# 31813A.net
KiCad netlist of a schematic drawn in EAGLE
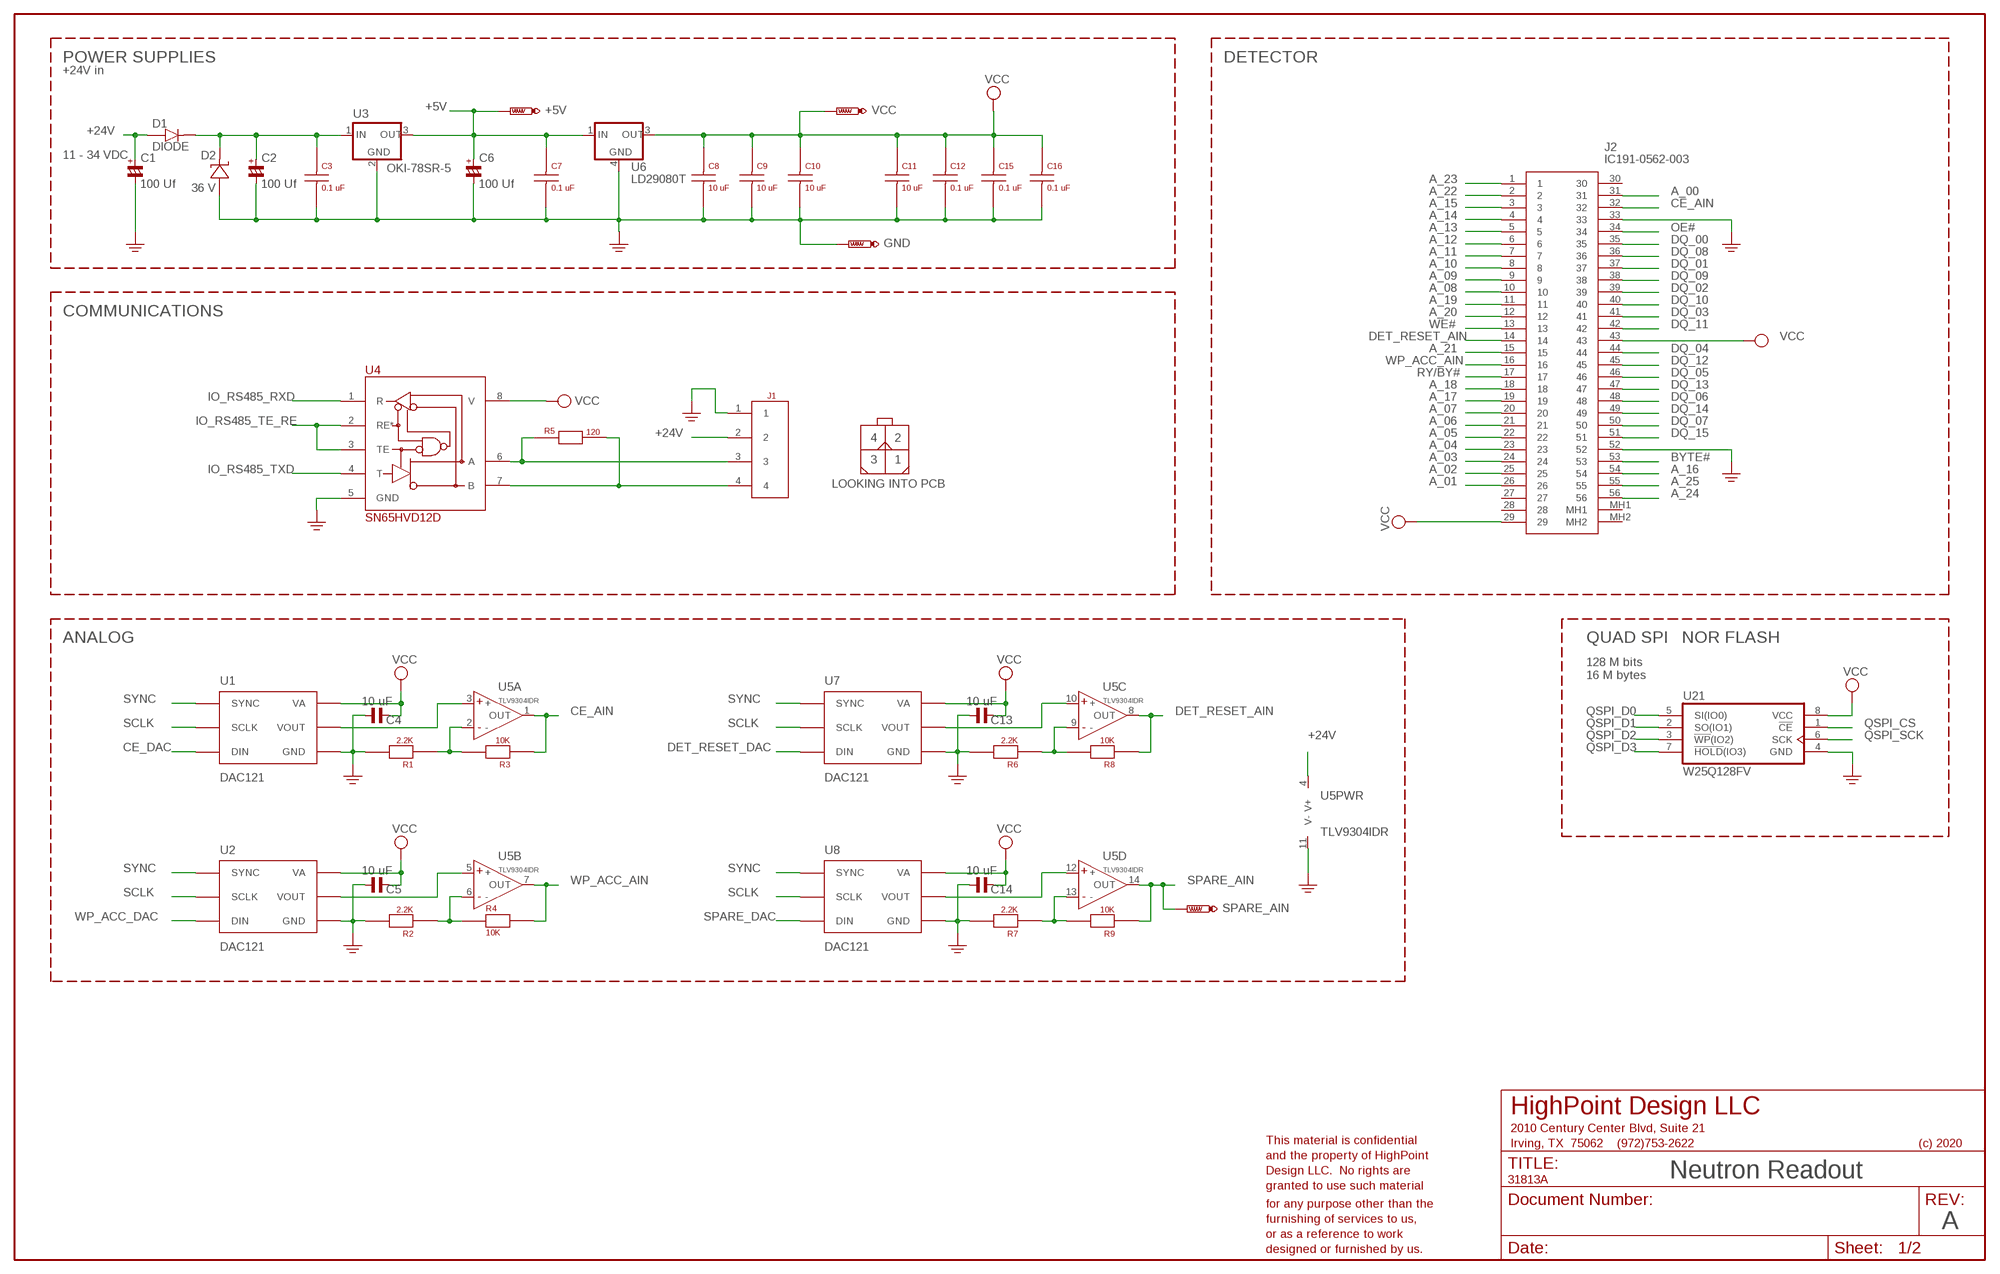
[diagram p0: schematic, sheet 1]
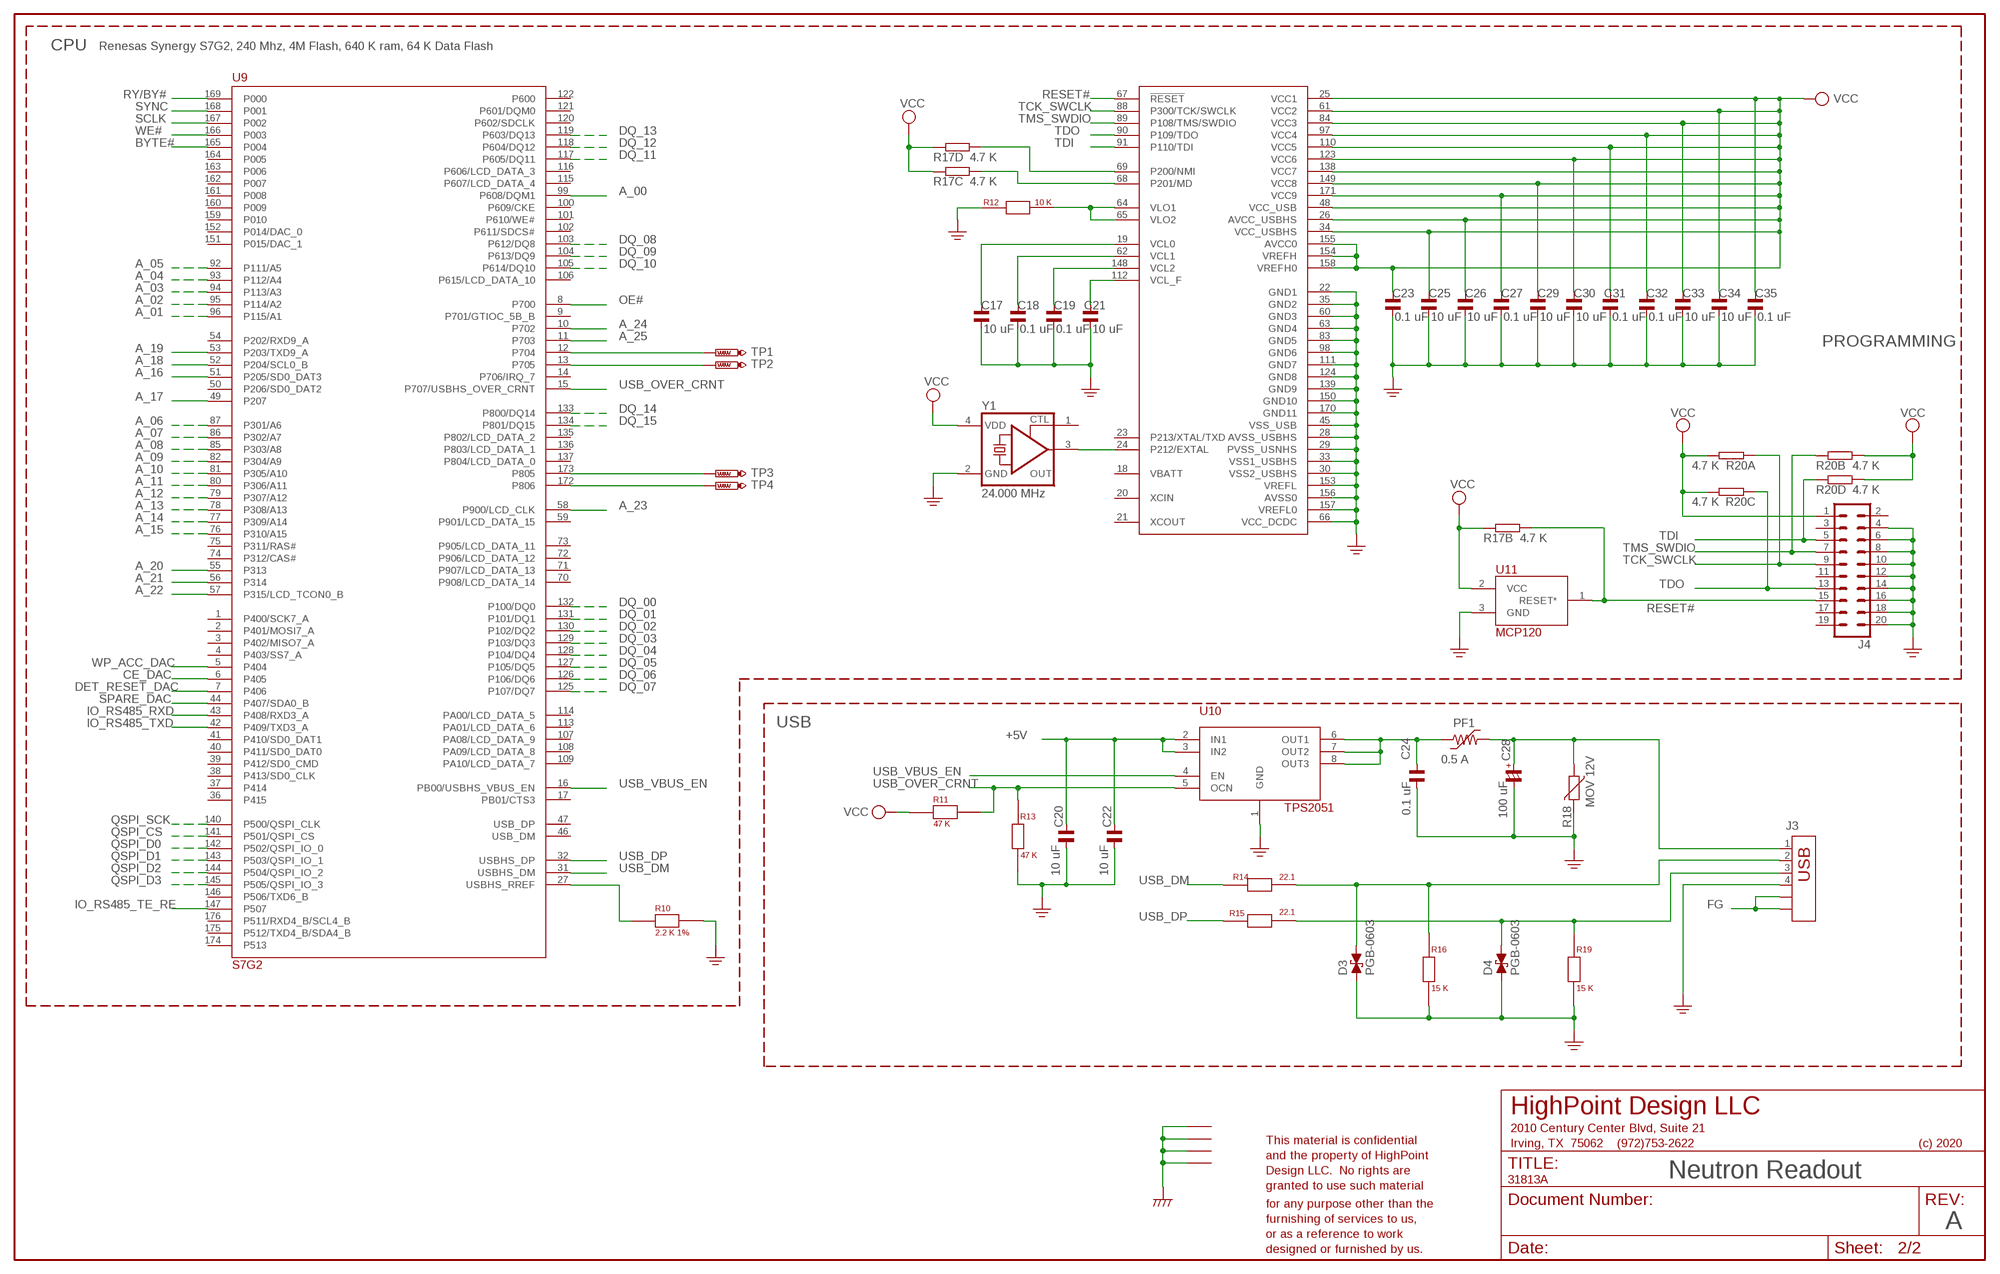
[diagram p1: schematic, sheet 2]

(export (version "E")
  (design (tool "Eeschema 10.0.6"))
  (components
    (comp (ref "C17")
      (value "10 uF")
      (footprint "eagle-import:0603")
      (libsource (lib "eagle-import") (part "CAP_SMD-0603"))
    )
    (comp (ref "C18")
      (value "0.1 uF")
      (footprint "eagle-import:0603")
      (libsource (lib "eagle-import") (part "CAP_SMD-0603"))
    )
    (comp (ref "C19")
      (value "0.1 uF")
      (footprint "eagle-import:0603")
      (libsource (lib "eagle-import") (part "CAP_SMD-0603"))
    )
    (comp (ref "C20")
      (value "10 uF")
      (footprint "eagle-import:0603")
      (libsource (lib "eagle-import") (part "CAP_SMD-0603"))
    )
    (comp (ref "C21")
      (value "10 uF")
      (footprint "eagle-import:0603")
      (libsource (lib "eagle-import") (part "CAP_SMD-0603"))
    )
    (comp (ref "C22")
      (value "10 uF")
      (footprint "eagle-import:0603")
      (libsource (lib "eagle-import") (part "CAP_SMD-0603"))
    )
    (comp (ref "C23")
      (value "0.1 uF")
      (footprint "eagle-import:0603")
      (libsource (lib "eagle-import") (part "CAP_SMD-0603"))
    )
    (comp (ref "C24")
      (value "0.1 uF")
      (footprint "eagle-import:0603")
      (libsource (lib "eagle-import") (part "CAP_SMD-0603"))
    )
    (comp (ref "C25")
      (value "10 uF")
      (footprint "eagle-import:0603")
      (libsource (lib "eagle-import") (part "CAP_SMD-0603"))
    )
    (comp (ref "C26")
      (value "10 uF")
      (footprint "eagle-import:0603")
      (libsource (lib "eagle-import") (part "CAP_SMD-0603"))
    )
    (comp (ref "C27")
      (value "0.1 uF")
      (footprint "eagle-import:0603")
      (libsource (lib "eagle-import") (part "CAP_SMD-0603"))
    )
    (comp (ref "C28")
      (value "100 uF")
      (footprint "eagle-import:CSV-E_F")
      (libsource (lib "eagle-import") (part "CAP_POL-E"))
    )
    (comp (ref "C29")
      (value "10 uF")
      (footprint "eagle-import:0603")
      (libsource (lib "eagle-import") (part "CAP_SMD-0603"))
    )
    (comp (ref "C30")
      (value "10 uF")
      (footprint "eagle-import:0603")
      (libsource (lib "eagle-import") (part "CAP_SMD-0603"))
    )
    (comp (ref "C31")
      (value "0.1 uF")
      (footprint "eagle-import:0603")
      (libsource (lib "eagle-import") (part "CAP_SMD-0603"))
    )
    (comp (ref "C32")
      (value "0.1 uF")
      (footprint "eagle-import:0603")
      (libsource (lib "eagle-import") (part "CAP_SMD-0603"))
    )
    (comp (ref "C33")
      (value "10 uF")
      (footprint "eagle-import:0603")
      (libsource (lib "eagle-import") (part "CAP_SMD-0603"))
    )
    (comp (ref "C34")
      (value "10 uF")
      (footprint "eagle-import:0603")
      (libsource (lib "eagle-import") (part "CAP_SMD-0603"))
    )
    (comp (ref "C35")
      (value "0.1 uF")
      (footprint "eagle-import:0603")
      (libsource (lib "eagle-import") (part "CAP_SMD-0603"))
    )
    (comp (ref "D3")
      (value "PGB-0603")
      (footprint "eagle-import:PGB-0603")
      (libsource (lib "eagle-import") (part "PGB-0603"))
    )
    (comp (ref "D4")
      (value "PGB-0603")
      (footprint "eagle-import:PGB-0603")
      (libsource (lib "eagle-import") (part "PGB-0603"))
    )
    (comp (ref "J3")
      (value "CON-USB-292303-1")
      (footprint "eagle-import:USB")
      (libsource (lib "eagle-import") (part "CON-USB-292303-1"))
    )
    (comp (ref "J4")
      (value "ML20")
      (footprint "eagle-import:ML20")
      (libsource (lib "eagle-import") (part "ML20"))
    )
    (comp (ref "M1")
      (value "MNT-125")
      (footprint "eagle-import:MNT-125")
      (libsource (lib "eagle-import") (part "MNT-125"))
    )
    (comp (ref "M2")
      (value "MNT-125")
      (footprint "eagle-import:MNT-125")
      (libsource (lib "eagle-import") (part "MNT-125"))
    )
    (comp (ref "M3")
      (value "MNT-125")
      (footprint "eagle-import:MNT-125")
      (libsource (lib "eagle-import") (part "MNT-125"))
    )
    (comp (ref "M4")
      (value "MNT-125")
      (footprint "eagle-import:MNT-125")
      (libsource (lib "eagle-import") (part "MNT-125"))
    )
    (comp (ref "PF1")
      (value "0.5 A")
      (footprint "eagle-import:F1206")
      (libsource (lib "eagle-import") (part "PTC-F1206"))
    )
    (comp (ref "R10")
      (value "2.2 K 1%")
      (footprint "eagle-import:0603")
      (libsource (lib "eagle-import") (part "RES-0603-H"))
    )
    (comp (ref "R11")
      (value "47 K")
      (footprint "eagle-import:0603")
      (libsource (lib "eagle-import") (part "RES-0603-H"))
    )
    (comp (ref "R12")
      (value "10 K")
      (footprint "eagle-import:0603")
      (libsource (lib "eagle-import") (part "RES-0603-H"))
    )
    (comp (ref "R13")
      (value "47 K")
      (footprint "eagle-import:0603")
      (libsource (lib "eagle-import") (part "RES-0603-V"))
    )
    (comp (ref "R14")
      (value "22.1")
      (footprint "eagle-import:0603")
      (libsource (lib "eagle-import") (part "RES-0603-H"))
    )
    (comp (ref "R15")
      (value "22.1")
      (footprint "eagle-import:0603")
      (libsource (lib "eagle-import") (part "RES-0603-H"))
    )
    (comp (ref "R16")
      (value "15 K")
      (footprint "eagle-import:0603")
      (libsource (lib "eagle-import") (part "RES-0603-V"))
    )
    (comp (ref "R17")
      (value "4.7 K")
      (footprint "eagle-import:RNET-4R-38V")
      (libsource (lib "eagle-import") (part "R_38V"))
    )
    (comp (ref "R18")
      (value "MOV 12V")
      (footprint "eagle-import:R0603")
      (libsource (lib "eagle-import") (part "VARISTOR-0603"))
    )
    (comp (ref "R19")
      (value "15 K")
      (footprint "eagle-import:0603")
      (libsource (lib "eagle-import") (part "RES-0603-V"))
    )
    (comp (ref "R20")
      (value "4.7 K")
      (footprint "eagle-import:RNET-4R-38V")
      (libsource (lib "eagle-import") (part "R_38V"))
    )
    (comp (ref "TP1")
      (value "TP")
      (footprint "eagle-import:TP8040")
      (libsource (lib "eagle-import") (part "TP"))
    )
    (comp (ref "TP2")
      (value "TP")
      (footprint "eagle-import:TP8040")
      (libsource (lib "eagle-import") (part "TP"))
    )
    (comp (ref "TP3")
      (value "TP")
      (footprint "eagle-import:TP8040")
      (libsource (lib "eagle-import") (part "TP"))
    )
    (comp (ref "TP4")
      (value "TP")
      (footprint "eagle-import:TP8040")
      (libsource (lib "eagle-import") (part "TP"))
    )
    (comp (ref "U9")
      (value "S7G2")
      (footprint "eagle-import:LQFP176")
      (libsource (lib "eagle-import") (part "S7G2-176"))
    )
    (comp (ref "U10")
      (value "TPS2051")
      (footprint "eagle-import:SOIC-8-SPECIAL")
      (libsource (lib "eagle-import") (part "TPS2051"))
    )
    (comp (ref "U11")
      (value "MCP120")
      (footprint "eagle-import:SOT23")
      (libsource (lib "eagle-import") (part "MCP120"))
    )
    (comp (ref "Y1")
      (value "24.000 MHz")
      (footprint "eagle-import:ASFL1")
      (libsource (lib "eagle-import") (part "ASFL1"))
    )
    (comp (ref "+5V")
      (value "TP")
      (footprint "eagle-import:TP8040")
      (libsource (lib "eagle-import") (part "TP"))
    )
    (comp (ref "C1")
      (value "100 Uf")
      (footprint "eagle-import:CSV-E_F")
      (libsource (lib "eagle-import") (part "CAP_POL-E"))
    )
    (comp (ref "C2")
      (value "100 Uf")
      (footprint "eagle-import:CSV-E_F")
      (libsource (lib "eagle-import") (part "CAP_POL-E"))
    )
    (comp (ref "C3")
      (value "0.1 uF")
      (footprint "eagle-import:0603")
      (libsource (lib "eagle-import") (part "CAP-0603"))
    )
    (comp (ref "C4")
      (value "10 uF")
      (footprint "eagle-import:0603")
      (libsource (lib "eagle-import") (part "31813 Neutron Readout PCB_CAP_SMD-0603"))
    )
    (comp (ref "C5")
      (value "10 uF")
      (footprint "eagle-import:0603")
      (libsource (lib "eagle-import") (part "31813 Neutron Readout PCB_CAP_SMD-0603"))
    )
    (comp (ref "C6")
      (value "100 Uf")
      (footprint "eagle-import:CSV-E_F")
      (libsource (lib "eagle-import") (part "CAP_POL-E"))
    )
    (comp (ref "C7")
      (value "0.1 uF")
      (footprint "eagle-import:0603")
      (libsource (lib "eagle-import") (part "CAP-0603"))
    )
    (comp (ref "C8")
      (value "10 uF")
      (footprint "eagle-import:0603")
      (libsource (lib "eagle-import") (part "CAP-0603"))
    )
    (comp (ref "C9")
      (value "10 uF")
      (footprint "eagle-import:0603")
      (libsource (lib "eagle-import") (part "CAP-0603"))
    )
    (comp (ref "C10")
      (value "10 uF")
      (footprint "eagle-import:0603")
      (libsource (lib "eagle-import") (part "CAP-0603"))
    )
    (comp (ref "C11")
      (value "10 uF")
      (footprint "eagle-import:0603")
      (libsource (lib "eagle-import") (part "CAP-0603"))
    )
    (comp (ref "C12")
      (value "0.1 uF")
      (footprint "eagle-import:0603")
      (libsource (lib "eagle-import") (part "CAP-0603"))
    )
    (comp (ref "C13")
      (value "10 uF")
      (footprint "eagle-import:0603")
      (libsource (lib "eagle-import") (part "31813 Neutron Readout PCB_CAP_SMD-0603"))
    )
    (comp (ref "C14")
      (value "10 uF")
      (footprint "eagle-import:0603")
      (libsource (lib "eagle-import") (part "31813 Neutron Readout PCB_CAP_SMD-0603"))
    )
    (comp (ref "C15")
      (value "0.1 uF")
      (footprint "eagle-import:0603")
      (libsource (lib "eagle-import") (part "CAP-0603"))
    )
    (comp (ref "C16")
      (value "0.1 uF")
      (footprint "eagle-import:0603")
      (libsource (lib "eagle-import") (part "CAP-0603"))
    )
    (comp (ref "D1")
      (value "DIODE")
      (footprint "eagle-import:SOD-123_MINI-SMA")
      (libsource (lib "eagle-import") (part "DIODE"))
    )
    (comp (ref "D2")
      (value "36 V")
      (footprint "eagle-import:SMB")
      (libsource (lib "eagle-import") (part "TRANSORB"))
    )
    (comp (ref "GND")
      (value "TP")
      (footprint "eagle-import:TP8040")
      (libsource (lib "eagle-import") (part "TP"))
    )
    (comp (ref "J1")
      (value "MICRO-FIT-4POS")
      (footprint "eagle-import:43045-0412")
      (libsource (lib "eagle-import") (part "MICRO-FIT-4POS"))
    )
    (comp (ref "J2")
      (value "IC191-0562-003")
      (footprint "eagle-import:IC1910562003")
      (fields (field (name "MOUSER_PART_NUMBER") "945-IC191-0562-003"))
      (libsource (lib "eagle-import") (part "IC191-0562-003"))
    )
    (comp (ref "R1")
      (value "2.2K")
      (footprint "eagle-import:0603")
      (libsource (lib "eagle-import") (part "31813 Neutron Readout PCB_RES-0603-H"))
    )
    (comp (ref "R2")
      (value "2.2K")
      (footprint "eagle-import:0603")
      (libsource (lib "eagle-import") (part "31813 Neutron Readout PCB_RES-0603-H"))
    )
    (comp (ref "R3")
      (value "10K")
      (footprint "eagle-import:0603")
      (libsource (lib "eagle-import") (part "31813 Neutron Readout PCB_RES-0603-H"))
    )
    (comp (ref "R4")
      (value "10K")
      (footprint "eagle-import:0603")
      (libsource (lib "eagle-import") (part "31813 Neutron Readout PCB_RES-0603-H"))
    )
    (comp (ref "R5")
      (value "120")
      (footprint "eagle-import:0603")
      (libsource (lib "eagle-import") (part "RES-0603-H"))
    )
    (comp (ref "R6")
      (value "2.2K")
      (footprint "eagle-import:0603")
      (libsource (lib "eagle-import") (part "31813 Neutron Readout PCB_RES-0603-H"))
    )
    (comp (ref "R7")
      (value "2.2K")
      (footprint "eagle-import:0603")
      (libsource (lib "eagle-import") (part "31813 Neutron Readout PCB_RES-0603-H"))
    )
    (comp (ref "R8")
      (value "10K")
      (footprint "eagle-import:0603")
      (libsource (lib "eagle-import") (part "31813 Neutron Readout PCB_RES-0603-H"))
    )
    (comp (ref "R9")
      (value "10K")
      (footprint "eagle-import:0603")
      (libsource (lib "eagle-import") (part "31813 Neutron Readout PCB_RES-0603-H"))
    )
    (comp (ref "SPARE_AIN")
      (value "TP")
      (footprint "eagle-import:TP8040")
      (libsource (lib "eagle-import") (part "TP"))
    )
    (comp (ref "U1")
      (value "DAC121")
      (footprint "eagle-import:SOT23-6")
      (libsource (lib "eagle-import") (part "DAC121"))
    )
    (comp (ref "U2")
      (value "DAC121")
      (footprint "eagle-import:SOT23-6")
      (libsource (lib "eagle-import") (part "DAC121"))
    )
    (comp (ref "U3")
      (value "OKI-78SR-5")
      (footprint "eagle-import:PS-OKI-78SR")
      (libsource (lib "eagle-import") (part "PS-OKI-78SR"))
    )
    (comp (ref "U4")
      (value "SN65HVD12D")
      (footprint "eagle-import:SOIC-08-150")
      (libsource (lib "eagle-import") (part "SN65HVD12D"))
    )
    (comp (ref "U5")
      (value "TLV9304IDR")
      (footprint "eagle-import:SO14")
      (libsource (lib "eagle-import") (part "TLV9304IDR"))
    )
    (comp (ref "U6")
      (value "LD29080T")
      (footprint "eagle-import:DPAK")
      (libsource (lib "eagle-import") (part "LD29080T"))
    )
    (comp (ref "U7")
      (value "DAC121")
      (footprint "eagle-import:SOT23-6")
      (libsource (lib "eagle-import") (part "DAC121"))
    )
    (comp (ref "U8")
      (value "DAC121")
      (footprint "eagle-import:SOT23-6")
      (libsource (lib "eagle-import") (part "DAC121"))
    )
    (comp (ref "U21")
      (value "W25Q128FV")
      (footprint "eagle-import:SO08-JB")
      (libsource (lib "eagle-import") (part "IS25LQ080B-JB"))
    )
    (comp (ref "VCC")
      (value "TP")
      (footprint "eagle-import:TP8040")
      (libsource (lib "eagle-import") (part "TP"))
    )
  )
  (nets
    (net (code "1") (name "+5V") (class "Default")
      (node (ref "+5V") (pin "1") (pinfunction "TP_1") (pintype "input"))
      (node (ref "C20") (pin "2") (pinfunction "2_2") (pintype "passive"))
      (node (ref "C22") (pin "2") (pinfunction "2_2") (pintype "passive"))
      (node (ref "C6") (pin "+") (pinfunction "+_+") (pintype "passive"))
      (node (ref "C7") (pin "1") (pinfunction "P$1_1") (pintype "bidirectional"))
      (node (ref "U10") (pin "2") (pinfunction "IN1_2") (pintype "bidirectional"))
      (node (ref "U10") (pin "3") (pinfunction "IN2_3") (pintype "bidirectional"))
      (node (ref "U3") (pin "3") (pinfunction "OUT_3") (pintype "passive"))
      (node (ref "U6") (pin "1") (pinfunction "IN_1") (pintype "input"))
    )
    (net (code "2") (name "+24V") (class "Default")
      (node (ref "C1") (pin "+") (pinfunction "+_+") (pintype "passive"))
      (node (ref "D1") (pin "A") (pinfunction "A_A") (pintype "passive"))
      (node (ref "J1") (pin "2") (pinfunction "2_2") (pintype "bidirectional"))
      (node (ref "U5") (pin "4") (pinfunction "V+_4") (pintype "power_in"))
    )
    (net (code "3") (name "A_00") (class "Default")
      (node (ref "J2") (pin "31") (pinfunction "31_31") (pintype "bidirectional"))
      (node (ref "U9") (pin "99") (pinfunction "P608/DQM1_99") (pintype "bidirectional"))
    )
    (net (code "4") (name "A_01") (class "Default")
      (node (ref "J2") (pin "26") (pinfunction "26_26") (pintype "bidirectional"))
      (node (ref "U9") (pin "96") (pinfunction "P115/A1_96") (pintype "bidirectional"))
    )
    (net (code "5") (name "A_02") (class "Default")
      (node (ref "J2") (pin "25") (pinfunction "25_25") (pintype "bidirectional"))
      (node (ref "U9") (pin "95") (pinfunction "P114/A2_95") (pintype "bidirectional"))
    )
    (net (code "6") (name "A_03") (class "Default")
      (node (ref "J2") (pin "24") (pinfunction "24_24") (pintype "bidirectional"))
      (node (ref "U9") (pin "94") (pinfunction "P113/A3_94") (pintype "bidirectional"))
    )
    (net (code "7") (name "A_04") (class "Default")
      (node (ref "J2") (pin "23") (pinfunction "23_23") (pintype "bidirectional"))
      (node (ref "U9") (pin "93") (pinfunction "P112/A4_93") (pintype "bidirectional"))
    )
    (net (code "8") (name "A_05") (class "Default")
      (node (ref "J2") (pin "22") (pinfunction "22_22") (pintype "bidirectional"))
      (node (ref "U9") (pin "92") (pinfunction "P111/A5_92") (pintype "bidirectional"))
    )
    (net (code "9") (name "A_06") (class "Default")
      (node (ref "J2") (pin "21") (pinfunction "21_21") (pintype "bidirectional"))
      (node (ref "U9") (pin "87") (pinfunction "P301/A6_87") (pintype "bidirectional"))
    )
    (net (code "10") (name "A_07") (class "Default")
      (node (ref "J2") (pin "20") (pinfunction "20_20") (pintype "bidirectional"))
      (node (ref "U9") (pin "86") (pinfunction "P302/A7_86") (pintype "bidirectional"))
    )
    (net (code "11") (name "A_08") (class "Default")
      (node (ref "J2") (pin "10") (pinfunction "10_10") (pintype "bidirectional"))
      (node (ref "U9") (pin "85") (pinfunction "P303/A8_85") (pintype "bidirectional"))
    )
    (net (code "12") (name "A_09") (class "Default")
      (node (ref "J2") (pin "9") (pinfunction "9_9") (pintype "bidirectional"))
      (node (ref "U9") (pin "82") (pinfunction "P304/A9_82") (pintype "bidirectional"))
    )
    (net (code "13") (name "A_10") (class "Default")
      (node (ref "J2") (pin "8") (pinfunction "8_8") (pintype "bidirectional"))
      (node (ref "U9") (pin "81") (pinfunction "P305/A10_81") (pintype "bidirectional"))
    )
    (net (code "14") (name "A_11") (class "Default")
      (node (ref "J2") (pin "7") (pinfunction "7_7") (pintype "bidirectional"))
      (node (ref "U9") (pin "80") (pinfunction "P306/A11_80") (pintype "bidirectional"))
    )
    (net (code "15") (name "A_12") (class "Default")
      (node (ref "J2") (pin "6") (pinfunction "6_6") (pintype "bidirectional"))
      (node (ref "U9") (pin "79") (pinfunction "P307/A12_79") (pintype "bidirectional"))
    )
    (net (code "16") (name "A_13") (class "Default")
      (node (ref "J2") (pin "5") (pinfunction "5_5") (pintype "bidirectional"))
      (node (ref "U9") (pin "78") (pinfunction "P308/A13_78") (pintype "bidirectional"))
    )
    (net (code "17") (name "A_14") (class "Default")
      (node (ref "J2") (pin "4") (pinfunction "4_4") (pintype "bidirectional"))
      (node (ref "U9") (pin "77") (pinfunction "P309/A14_77") (pintype "bidirectional"))
    )
    (net (code "18") (name "A_15") (class "Default")
      (node (ref "J2") (pin "3") (pinfunction "3_3") (pintype "bidirectional"))
      (node (ref "U9") (pin "76") (pinfunction "P310/A15_76") (pintype "bidirectional"))
    )
    (net (code "19") (name "A_16") (class "Default")
      (node (ref "J2") (pin "54") (pinfunction "54_54") (pintype "bidirectional"))
      (node (ref "U9") (pin "51") (pinfunction "P205/SD0_DAT3_51") (pintype "bidirectional"))
    )
    (net (code "20") (name "A_17") (class "Default")
      (node (ref "J2") (pin "19") (pinfunction "19_19") (pintype "bidirectional"))
      (node (ref "U9") (pin "49") (pinfunction "P207_49") (pintype "bidirectional"))
    )
    (net (code "21") (name "A_18") (class "Default")
      (node (ref "J2") (pin "18") (pinfunction "18_18") (pintype "bidirectional"))
      (node (ref "U9") (pin "52") (pinfunction "P204/SCL0_B_52") (pintype "bidirectional"))
    )
    (net (code "22") (name "A_19") (class "Default")
      (node (ref "J2") (pin "11") (pinfunction "11_11") (pintype "bidirectional"))
      (node (ref "U9") (pin "53") (pinfunction "P203/TXD9_A_53") (pintype "bidirectional"))
    )
    (net (code "23") (name "A_20") (class "Default")
      (node (ref "J2") (pin "12") (pinfunction "12_12") (pintype "bidirectional"))
      (node (ref "U9") (pin "55") (pinfunction "P313_55") (pintype "bidirectional"))
    )
    (net (code "24") (name "A_21") (class "Default")
      (node (ref "J2") (pin "15") (pinfunction "15_15") (pintype "bidirectional"))
      (node (ref "U9") (pin "56") (pinfunction "P314_56") (pintype "bidirectional"))
    )
    (net (code "25") (name "A_22") (class "Default")
      (node (ref "J2") (pin "2") (pinfunction "2_2") (pintype "bidirectional"))
      (node (ref "U9") (pin "57") (pinfunction "P315/LCD_TCON0_B_57") (pintype "bidirectional"))
    )
    (net (code "26") (name "A_23") (class "Default")
      (node (ref "J2") (pin "1") (pinfunction "1_1") (pintype "bidirectional"))
      (node (ref "U9") (pin "58") (pinfunction "P900/LCD_CLK_58") (pintype "bidirectional"))
    )
    (net (code "27") (name "A_24") (class "Default")
      (node (ref "J2") (pin "56") (pinfunction "56_56") (pintype "bidirectional"))
      (node (ref "U9") (pin "10") (pinfunction "P702_10") (pintype "bidirectional"))
    )
    (net (code "28") (name "A_25") (class "Default")
      (node (ref "J2") (pin "55") (pinfunction "55_55") (pintype "bidirectional"))
      (node (ref "U9") (pin "11") (pinfunction "P703_11") (pintype "bidirectional"))
    )
    (net (code "29") (name "BYTE#") (class "Default")
      (node (ref "J2") (pin "53") (pinfunction "53_53") (pintype "bidirectional"))
      (node (ref "U9") (pin "165") (pinfunction "P004_165") (pintype "bidirectional"))
    )
    (net (code "30") (name "CE_AIN") (class "Default")
      (node (ref "J2") (pin "32") (pinfunction "32_32") (pintype "bidirectional"))
      (node (ref "R3") (pin "1") (pinfunction "P$1_1") (pintype "bidirectional"))
      (node (ref "U5") (pin "1") (pinfunction "OUT_1") (pintype "output"))
    )
    (net (code "31") (name "CE_DAC") (class "Default")
      (node (ref "U1") (pin "4") (pinfunction "DIN_4") (pintype "input"))
      (node (ref "U9") (pin "6") (pinfunction "P405_6") (pintype "bidirectional"))
    )
    (net (code "32") (name "DET_RESET_AIN") (class "Default")
      (node (ref "J2") (pin "14") (pinfunction "14_14") (pintype "bidirectional"))
      (node (ref "R8") (pin "1") (pinfunction "P$1_1") (pintype "bidirectional"))
      (node (ref "U5") (pin "8") (pinfunction "OUT_8") (pintype "output"))
    )
    (net (code "33") (name "DET_RESET_DAC") (class "Default")
      (node (ref "U7") (pin "4") (pinfunction "DIN_4") (pintype "input"))
      (node (ref "U9") (pin "7") (pinfunction "P406_7") (pintype "bidirectional"))
    )
    (net (code "34") (name "DQ_00") (class "Default")
      (node (ref "J2") (pin "35") (pinfunction "35_35") (pintype "bidirectional"))
      (node (ref "U9") (pin "132") (pinfunction "P100/DQ0_132") (pintype "bidirectional"))
    )
    (net (code "35") (name "DQ_01") (class "Default")
      (node (ref "J2") (pin "37") (pinfunction "37_37") (pintype "bidirectional"))
      (node (ref "U9") (pin "131") (pinfunction "P101/DQ1_131") (pintype "bidirectional"))
    )
    (net (code "36") (name "DQ_02") (class "Default")
      (node (ref "J2") (pin "39") (pinfunction "39_39") (pintype "bidirectional"))
      (node (ref "U9") (pin "130") (pinfunction "P102/DQ2_130") (pintype "bidirectional"))
    )
    (net (code "37") (name "DQ_03") (class "Default")
      (node (ref "J2") (pin "41") (pinfunction "41_41") (pintype "bidirectional"))
      (node (ref "U9") (pin "129") (pinfunction "P103/DQ3_129") (pintype "bidirectional"))
    )
    (net (code "38") (name "DQ_04") (class "Default")
      (node (ref "J2") (pin "44") (pinfunction "44_44") (pintype "bidirectional"))
      (node (ref "U9") (pin "128") (pinfunction "P104/DQ4_128") (pintype "bidirectional"))
    )
    (net (code "39") (name "DQ_05") (class "Default")
      (node (ref "J2") (pin "46") (pinfunction "46_46") (pintype "bidirectional"))
      (node (ref "U9") (pin "127") (pinfunction "P105/DQ5_127") (pintype "bidirectional"))
    )
    (net (code "40") (name "DQ_06") (class "Default")
      (node (ref "J2") (pin "48") (pinfunction "48_48") (pintype "bidirectional"))
      (node (ref "U9") (pin "126") (pinfunction "P106/DQ6_126") (pintype "bidirectional"))
    )
    (net (code "41") (name "DQ_07") (class "Default")
      (node (ref "J2") (pin "50") (pinfunction "50_50") (pintype "bidirectional"))
      (node (ref "U9") (pin "125") (pinfunction "P107/DQ7_125") (pintype "bidirectional"))
    )
    (net (code "42") (name "DQ_08") (class "Default")
      (node (ref "J2") (pin "36") (pinfunction "36_36") (pintype "bidirectional"))
      (node (ref "U9") (pin "103") (pinfunction "P612/DQ8_103") (pintype "bidirectional"))
    )
    (net (code "43") (name "DQ_09") (class "Default")
      (node (ref "J2") (pin "38") (pinfunction "38_38") (pintype "bidirectional"))
      (node (ref "U9") (pin "104") (pinfunction "P613/DQ9_104") (pintype "bidirectional"))
    )
    (net (code "44") (name "DQ_10") (class "Default")
      (node (ref "J2") (pin "40") (pinfunction "40_40") (pintype "bidirectional"))
      (node (ref "U9") (pin "105") (pinfunction "P614/DQ10_105") (pintype "bidirectional"))
    )
    (net (code "45") (name "DQ_11") (class "Default")
      (node (ref "J2") (pin "42") (pinfunction "42_42") (pintype "bidirectional"))
      (node (ref "U9") (pin "117") (pinfunction "P605/DQ11_117") (pintype "bidirectional"))
    )
    (net (code "46") (name "DQ_12") (class "Default")
      (node (ref "J2") (pin "45") (pinfunction "45_45") (pintype "bidirectional"))
      (node (ref "U9") (pin "118") (pinfunction "P604/DQ12_118") (pintype "bidirectional"))
    )
    (net (code "47") (name "DQ_13") (class "Default")
      (node (ref "J2") (pin "47") (pinfunction "47_47") (pintype "bidirectional"))
      (node (ref "U9") (pin "119") (pinfunction "P603/DQ13_119") (pintype "bidirectional"))
    )
    (net (code "48") (name "DQ_14") (class "Default")
      (node (ref "J2") (pin "49") (pinfunction "49_49") (pintype "bidirectional"))
      (node (ref "U9") (pin "133") (pinfunction "P800/DQ14_133") (pintype "bidirectional"))
    )
    (net (code "49") (name "DQ_15") (class "Default")
      (node (ref "J2") (pin "51") (pinfunction "51_51") (pintype "bidirectional"))
      (node (ref "U9") (pin "134") (pinfunction "P801/DQ15_134") (pintype "bidirectional"))
    )
    (net (code "50") (name "FG") (class "Default")
      (node (ref "J3") (pin "S1") (pinfunction "S1_S1") (pintype "passive"))
      (node (ref "J3") (pin "S2") (pinfunction "S2_S2") (pintype "passive"))
      (node (ref "M1") (pin "1") (pinfunction "1_1") (pintype "bidirectional"))
      (node (ref "M2") (pin "1") (pinfunction "1_1") (pintype "bidirectional"))
      (node (ref "M3") (pin "1") (pinfunction "1_1") (pintype "bidirectional"))
      (node (ref "M4") (pin "1") (pinfunction "1_1") (pintype "bidirectional"))
    )
    (net (code "51") (name "GND") (class "Default")
      (node (ref "C1") (pin "-") (pinfunction "-_-") (pintype "passive"))
      (node (ref "C10") (pin "2") (pinfunction "P$2_2") (pintype "bidirectional"))
      (node (ref "C11") (pin "2") (pinfunction "P$2_2") (pintype "bidirectional"))
      (node (ref "C12") (pin "2") (pinfunction "P$2_2") (pintype "bidirectional"))
      (node (ref "C13") (pin "1") (pinfunction "1_1") (pintype "passive"))
      (node (ref "C14") (pin "1") (pinfunction "1_1") (pintype "passive"))
      (node (ref "C15") (pin "2") (pinfunction "P$2_2") (pintype "bidirectional"))
      (node (ref "C16") (pin "2") (pinfunction "P$2_2") (pintype "bidirectional"))
      (node (ref "C17") (pin "1") (pinfunction "1_1") (pintype "passive"))
      (node (ref "C18") (pin "1") (pinfunction "1_1") (pintype "passive"))
      (node (ref "C19") (pin "1") (pinfunction "1_1") (pintype "passive"))
      (node (ref "C2") (pin "-") (pinfunction "-_-") (pintype "passive"))
      (node (ref "C20") (pin "1") (pinfunction "1_1") (pintype "passive"))
      (node (ref "C21") (pin "1") (pinfunction "1_1") (pintype "passive"))
      (node (ref "C22") (pin "1") (pinfunction "1_1") (pintype "passive"))
      (node (ref "C23") (pin "1") (pinfunction "1_1") (pintype "passive"))
      (node (ref "C24") (pin "1") (pinfunction "1_1") (pintype "passive"))
      (node (ref "C25") (pin "1") (pinfunction "1_1") (pintype "passive"))
      (node (ref "C26") (pin "1") (pinfunction "1_1") (pintype "passive"))
      (node (ref "C27") (pin "1") (pinfunction "1_1") (pintype "passive"))
      (node (ref "C28") (pin "-") (pinfunction "-_-") (pintype "passive"))
      (node (ref "C29") (pin "1") (pinfunction "1_1") (pintype "passive"))
      (node (ref "C3") (pin "2") (pinfunction "P$2_2") (pintype "bidirectional"))
      (node (ref "C30") (pin "1") (pinfunction "1_1") (pintype "passive"))
      (node (ref "C31") (pin "1") (pinfunction "1_1") (pintype "passive"))
      (node (ref "C32") (pin "1") (pinfunction "1_1") (pintype "passive"))
      (node (ref "C33") (pin "1") (pinfunction "1_1") (pintype "passive"))
      (node (ref "C34") (pin "1") (pinfunction "1_1") (pintype "passive"))
      (node (ref "C35") (pin "1") (pinfunction "1_1") (pintype "passive"))
      (node (ref "C4") (pin "1") (pinfunction "1_1") (pintype "passive"))
      (node (ref "C5") (pin "1") (pinfunction "1_1") (pintype "passive"))
      (node (ref "C6") (pin "-") (pinfunction "-_-") (pintype "passive"))
      (node (ref "C7") (pin "2") (pinfunction "P$2_2") (pintype "bidirectional"))
      (node (ref "C8") (pin "2") (pinfunction "P$2_2") (pintype "bidirectional"))
      (node (ref "C9") (pin "2") (pinfunction "P$2_2") (pintype "bidirectional"))
      (node (ref "D2") (pin "A") (pinfunction "A_A") (pintype "passive"))
      (node (ref "D3") (pin "1") (pinfunction "1_1") (pintype "passive"))
      (node (ref "D4") (pin "1") (pinfunction "1_1") (pintype "passive"))
      (node (ref "GND") (pin "1") (pinfunction "TP_1") (pintype "input"))
      (node (ref "J1") (pin "1") (pinfunction "1_1") (pintype "bidirectional"))
      (node (ref "J2") (pin "33") (pinfunction "33_33") (pintype "bidirectional"))
      (node (ref "J2") (pin "52") (pinfunction "52_52") (pintype "bidirectional"))
      (node (ref "J3") (pin "4") (pinfunction "4_4") (pintype "passive"))
      (node (ref "J4") (pin "10") (pinfunction "10_10") (pintype "passive"))
      (node (ref "J4") (pin "12") (pinfunction "12_12") (pintype "passive"))
      (node (ref "J4") (pin "14") (pinfunction "14_14") (pintype "passive"))
      (node (ref "J4") (pin "16") (pinfunction "16_16") (pintype "passive"))
      (node (ref "J4") (pin "18") (pinfunction "18_18") (pintype "passive"))
      (node (ref "J4") (pin "20") (pinfunction "20_20") (pintype "passive"))
      (node (ref "J4") (pin "4") (pinfunction "4_4") (pintype "passive"))
      (node (ref "J4") (pin "6") (pinfunction "6_6") (pintype "passive"))
      (node (ref "J4") (pin "8") (pinfunction "8_8") (pintype "passive"))
      (node (ref "R1") (pin "2") (pinfunction "P$2_2") (pintype "bidirectional"))
      (node (ref "R10") (pin "2") (pinfunction "P$2_2") (pintype "bidirectional"))
      (node (ref "R12") (pin "1") (pinfunction "P$1_1") (pintype "bidirectional"))
      (node (ref "R13") (pin "1") (pinfunction "P$1_1") (pintype "bidirectional"))
      (node (ref "R16") (pin "1") (pinfunction "P$1_1") (pintype "bidirectional"))
      (node (ref "R18") (pin "2") (pinfunction "2_2") (pintype "passive"))
      (node (ref "R19") (pin "1") (pinfunction "P$1_1") (pintype "bidirectional"))
      (node (ref "R2") (pin "2") (pinfunction "P$2_2") (pintype "bidirectional"))
      (node (ref "R6") (pin "2") (pinfunction "P$2_2") (pintype "bidirectional"))
      (node (ref "R7") (pin "2") (pinfunction "P$2_2") (pintype "bidirectional"))
      (node (ref "U1") (pin "2") (pinfunction "GND_2") (pintype "power_in"))
      (node (ref "U10") (pin "1") (pinfunction "GND_1") (pintype "bidirectional"))
      (node (ref "U11") (pin "3") (pinfunction "GND_3") (pintype "bidirectional"))
      (node (ref "U2") (pin "2") (pinfunction "GND_2") (pintype "power_in"))
      (node (ref "U21") (pin "4") (pinfunction "GND_4") (pintype "power_in"))
      (node (ref "U3") (pin "2") (pinfunction "GND_2") (pintype "input"))
      (node (ref "U4") (pin "5") (pinfunction "GND_5") (pintype "bidirectional"))
      (node (ref "U5") (pin "11") (pinfunction "V-_11") (pintype "power_in"))
      (node (ref "U6") (pin "4") (pinfunction "GND_4") (pintype "input"))
      (node (ref "U7") (pin "2") (pinfunction "GND_2") (pintype "power_in"))
      (node (ref "U8") (pin "2") (pinfunction "GND_2") (pintype "power_in"))
      (node (ref "U9") (pin "111") (pinfunction "GND7_111") (pintype "bidirectional"))
      (node (ref "U9") (pin "124") (pinfunction "GND8_124") (pintype "bidirectional"))
      (node (ref "U9") (pin "139") (pinfunction "GND9_139") (pintype "bidirectional"))
      (node (ref "U9") (pin "150") (pinfunction "GND10_150") (pintype "bidirectional"))
      (node (ref "U9") (pin "153") (pinfunction "VREFL_153") (pintype "bidirectional"))
      (node (ref "U9") (pin "156") (pinfunction "AVSS0_156") (pintype "bidirectional"))
      (node (ref "U9") (pin "157") (pinfunction "VREFL0_157") (pintype "bidirectional"))
      (node (ref "U9") (pin "170") (pinfunction "GND11_170") (pintype "bidirectional"))
      (node (ref "U9") (pin "22") (pinfunction "GND1_22") (pintype "bidirectional"))
      (node (ref "U9") (pin "28") (pinfunction "AVSS_USBHS_28") (pintype "bidirectional"))
      (node (ref "U9") (pin "29") (pinfunction "PVSS_USNHS_29") (pintype "bidirectional"))
      (node (ref "U9") (pin "30") (pinfunction "VSS2_USBHS_30") (pintype "bidirectional"))
      (node (ref "U9") (pin "33") (pinfunction "VSS1_USBHS_33") (pintype "bidirectional"))
      (node (ref "U9") (pin "35") (pinfunction "GND2_35") (pintype "bidirectional"))
      (node (ref "U9") (pin "45") (pinfunction "VSS_USB_45") (pintype "bidirectional"))
      (node (ref "U9") (pin "60") (pinfunction "GND3_60") (pintype "bidirectional"))
      (node (ref "U9") (pin "63") (pinfunction "GND4_63") (pintype "bidirectional"))
      (node (ref "U9") (pin "66") (pinfunction "VCC_DCDC_66") (pintype "bidirectional"))
      (node (ref "U9") (pin "83") (pinfunction "GND5_83") (pintype "bidirectional"))
      (node (ref "U9") (pin "98") (pinfunction "GND6_98") (pintype "bidirectional"))
      (node (ref "Y1") (pin "2") (pinfunction "GND_2") (pintype "power_in"))
    )
    (net (code "52") (name "IO_RS485_RXD") (class "Default")
      (node (ref "U4") (pin "1") (pinfunction "R_1") (pintype "bidirectional"))
      (node (ref "U9") (pin "43") (pinfunction "P408/RXD3_A_43") (pintype "bidirectional"))
    )
    (net (code "53") (name "IO_RS485_TE_RE") (class "Default")
      (node (ref "U4") (pin "2") (pinfunction "RE*_2") (pintype "bidirectional"))
      (node (ref "U4") (pin "3") (pinfunction "TE_3") (pintype "bidirectional"))
      (node (ref "U9") (pin "147") (pinfunction "P507_147") (pintype "bidirectional"))
    )
    (net (code "54") (name "IO_RS485_TXD") (class "Default")
      (node (ref "U4") (pin "4") (pinfunction "T_4") (pintype "bidirectional"))
      (node (ref "U9") (pin "42") (pinfunction "P409/TXD3_A_42") (pintype "bidirectional"))
    )
    (net (code "55") (name "Net-(C3-P$1)") (class "Default")
      (node (ref "C2") (pin "+") (pinfunction "+_+") (pintype "passive"))
      (node (ref "C3") (pin "1") (pinfunction "P$1_1") (pintype "bidirectional"))
      (node (ref "D1") (pin "C") (pinfunction "C_C") (pintype "passive"))
      (node (ref "D2") (pin "C") (pinfunction "C_C") (pintype "passive"))
      (node (ref "U3") (pin "1") (pinfunction "IN_1") (pintype "input"))
    )
    (net (code "56") (name "Net-(C28-Pad+)") (class "Default")
      (node (ref "C28") (pin "+") (pinfunction "+_+") (pintype "passive"))
      (node (ref "J3") (pin "1") (pinfunction "1_1") (pintype "passive"))
      (node (ref "PF1") (pin "2") (pinfunction "2_2") (pintype "passive"))
      (node (ref "R18") (pin "1") (pinfunction "1_1") (pintype "passive"))
    )
    (net (code "57") (name "Net-(R1-P$1)") (class "Default")
      (node (ref "R1") (pin "1") (pinfunction "P$1_1") (pintype "bidirectional"))
      (node (ref "R3") (pin "2") (pinfunction "P$2_2") (pintype "bidirectional"))
      (node (ref "U5") (pin "2") (pinfunction "-_2") (pintype "input"))
    )
    (net (code "58") (name "Net-(R2-P$1)") (class "Default")
      (node (ref "R2") (pin "1") (pinfunction "P$1_1") (pintype "bidirectional"))
      (node (ref "R4") (pin "1") (pinfunction "P$1_1") (pintype "bidirectional"))
      (node (ref "U5") (pin "6") (pinfunction "-_6") (pintype "input"))
    )
    (net (code "59") (name "Net-(R5-P$1)") (class "Default")
      (node (ref "J1") (pin "3") (pinfunction "3_3") (pintype "bidirectional"))
      (node (ref "R5") (pin "1") (pinfunction "P$1_1") (pintype "bidirectional"))
      (node (ref "U4") (pin "6") (pinfunction "A_6") (pintype "bidirectional"))
    )
    (net (code "60") (name "Net-(R5-P$2)") (class "Default")
      (node (ref "J1") (pin "4") (pinfunction "4_4") (pintype "bidirectional"))
      (node (ref "R5") (pin "2") (pinfunction "P$2_2") (pintype "bidirectional"))
      (node (ref "U4") (pin "7") (pinfunction "B_7") (pintype "bidirectional"))
    )
    (net (code "61") (name "Net-(R6-P$1)") (class "Default")
      (node (ref "R6") (pin "1") (pinfunction "P$1_1") (pintype "bidirectional"))
      (node (ref "R8") (pin "2") (pinfunction "P$2_2") (pintype "bidirectional"))
      (node (ref "U5") (pin "9") (pinfunction "-_9") (pintype "input"))
    )
    (net (code "62") (name "Net-(R7-P$1)") (class "Default")
      (node (ref "R7") (pin "1") (pinfunction "P$1_1") (pintype "bidirectional"))
      (node (ref "R9") (pin "2") (pinfunction "P$2_2") (pintype "bidirectional"))
      (node (ref "U5") (pin "13") (pinfunction "-_13") (pintype "input"))
    )
    (net (code "63") (name "Net-(R10-P$1)") (class "Default")
      (node (ref "R10") (pin "1") (pinfunction "P$1_1") (pintype "bidirectional"))
      (node (ref "U9") (pin "27") (pinfunction "USBHS_RREF_27") (pintype "bidirectional"))
    )
    (net (code "64") (name "Net-(R12-P$2)") (class "Default")
      (node (ref "R12") (pin "2") (pinfunction "P$2_2") (pintype "bidirectional"))
      (node (ref "U9") (pin "64") (pinfunction "VLO1_64") (pintype "bidirectional"))
      (node (ref "U9") (pin "65") (pinfunction "VLO2_65") (pintype "bidirectional"))
    )
    (net (code "65") (name "Net-(R14-P$2)") (class "Default")
      (node (ref "D3") (pin "2") (pinfunction "2_2") (pintype "passive"))
      (node (ref "J3") (pin "2") (pinfunction "2_2") (pintype "passive"))
      (node (ref "R14") (pin "2") (pinfunction "P$2_2") (pintype "bidirectional"))
      (node (ref "R16") (pin "2") (pinfunction "P$2_2") (pintype "bidirectional"))
    )
    (net (code "66") (name "Net-(R15-P$2)") (class "Default")
      (node (ref "D4") (pin "2") (pinfunction "2_2") (pintype "passive"))
      (node (ref "J3") (pin "3") (pinfunction "3_3") (pintype "passive"))
      (node (ref "R15") (pin "2") (pinfunction "P$2_2") (pintype "bidirectional"))
      (node (ref "R19") (pin "2") (pinfunction "P$2_2") (pintype "bidirectional"))
    )
    (net (code "67") (name "Net-(R17C-2)") (class "Default")
      (node (ref "R17") (pin "6") (pinfunction "2_6") (pintype "passive"))
      (node (ref "U9") (pin "68") (pinfunction "P201/MD_68") (pintype "bidirectional"))
    )
    (net (code "68") (name "Net-(R17D-2)") (class "Default")
      (node (ref "R17") (pin "5") (pinfunction "2_5") (pintype "passive"))
      (node (ref "U9") (pin "69") (pinfunction "P200/NMI_69") (pintype "bidirectional"))
    )
    (net (code "69") (name "Net-(TP1-TP)") (class "Default")
      (node (ref "TP1") (pin "1") (pinfunction "TP_1") (pintype "input"))
      (node (ref "U9") (pin "12") (pinfunction "P704_12") (pintype "bidirectional"))
    )
    (net (code "70") (name "Net-(TP2-TP)") (class "Default")
      (node (ref "TP2") (pin "1") (pinfunction "TP_1") (pintype "input"))
      (node (ref "U9") (pin "13") (pinfunction "P705_13") (pintype "bidirectional"))
    )
    (net (code "71") (name "Net-(TP3-TP)") (class "Default")
      (node (ref "TP3") (pin "1") (pinfunction "TP_1") (pintype "input"))
      (node (ref "U9") (pin "173") (pinfunction "P805_173") (pintype "bidirectional"))
    )
    (net (code "72") (name "Net-(TP4-TP)") (class "Default")
      (node (ref "TP4") (pin "1") (pinfunction "TP_1") (pintype "input"))
      (node (ref "U9") (pin "172") (pinfunction "P806_172") (pintype "bidirectional"))
    )
    (net (code "73") (name "Net-(U1-VOUT)") (class "Default")
      (node (ref "U1") (pin "1") (pinfunction "VOUT_1") (pintype "output"))
      (node (ref "U5") (pin "3") (pinfunction "+_3") (pintype "input"))
    )
    (net (code "74") (name "Net-(U2-VOUT)") (class "Default")
      (node (ref "U2") (pin "1") (pinfunction "VOUT_1") (pintype "output"))
      (node (ref "U5") (pin "5") (pinfunction "+_5") (pintype "input"))
    )
    (net (code "75") (name "Net-(U5C-+)") (class "Default")
      (node (ref "U5") (pin "10") (pinfunction "+_10") (pintype "input"))
      (node (ref "U7") (pin "1") (pinfunction "VOUT_1") (pintype "output"))
    )
    (net (code "76") (name "Net-(U5D-+)") (class "Default")
      (node (ref "U5") (pin "12") (pinfunction "+_12") (pintype "input"))
      (node (ref "U8") (pin "1") (pinfunction "VOUT_1") (pintype "output"))
    )
    (net (code "77") (name "Net-(U9-P212{slash}EXTAL)") (class "Default")
      (node (ref "U9") (pin "24") (pinfunction "P212/EXTAL_24") (pintype "bidirectional"))
      (node (ref "Y1") (pin "3") (pinfunction "OUT_3") (pintype "output"))
    )
    (net (code "78") (name "Net-(U9-VCL0)") (class "Default")
      (node (ref "C17") (pin "2") (pinfunction "2_2") (pintype "passive"))
      (node (ref "U9") (pin "19") (pinfunction "VCL0_19") (pintype "bidirectional"))
    )
    (net (code "79") (name "Net-(U9-VCL1)") (class "Default")
      (node (ref "C18") (pin "2") (pinfunction "2_2") (pintype "passive"))
      (node (ref "U9") (pin "62") (pinfunction "VCL1_62") (pintype "bidirectional"))
    )
    (net (code "80") (name "Net-(U9-VCL2)") (class "Default")
      (node (ref "C19") (pin "2") (pinfunction "2_2") (pintype "passive"))
      (node (ref "U9") (pin "148") (pinfunction "VCL2_148") (pintype "bidirectional"))
    )
    (net (code "81") (name "Net-(U9-VCL_F)") (class "Default")
      (node (ref "C21") (pin "2") (pinfunction "2_2") (pintype "passive"))
      (node (ref "U9") (pin "112") (pinfunction "VCL_F_112") (pintype "bidirectional"))
    )
    (net (code "82") (name "Net-(U10-OUT1)") (class "Default")
      (node (ref "C24") (pin "2") (pinfunction "2_2") (pintype "passive"))
      (node (ref "PF1") (pin "1") (pinfunction "1_1") (pintype "passive"))
      (node (ref "U10") (pin "6") (pinfunction "OUT1_6") (pintype "bidirectional"))
      (node (ref "U10") (pin "7") (pinfunction "OUT2_7") (pintype "bidirectional"))
      (node (ref "U10") (pin "8") (pinfunction "OUT3_8") (pintype "bidirectional"))
    )
    (net (code "83") (name "OE#") (class "Default")
      (node (ref "J2") (pin "34") (pinfunction "34_34") (pintype "bidirectional"))
      (node (ref "U9") (pin "8") (pinfunction "P700_8") (pintype "bidirectional"))
    )
    (net (code "84") (name "QSPI_CS") (class "Default")
      (node (ref "U21") (pin "1") (pinfunction "~{CE}_1") (pintype "input"))
      (node (ref "U9") (pin "141") (pinfunction "P501/QSPI_CS_141") (pintype "bidirectional"))
    )
    (net (code "85") (name "QSPI_D0") (class "Default")
      (node (ref "U21") (pin "5") (pinfunction "SI(IO0)_5") (pintype "bidirectional"))
      (node (ref "U9") (pin "142") (pinfunction "P502/QSPI_IO_0_142") (pintype "bidirectional"))
    )
    (net (code "86") (name "QSPI_D1") (class "Default")
      (node (ref "U21") (pin "2") (pinfunction "SO(IO1)_2") (pintype "bidirectional"))
      (node (ref "U9") (pin "143") (pinfunction "P503/QSPI_IO_1_143") (pintype "bidirectional"))
    )
    (net (code "87") (name "QSPI_D2") (class "Default")
      (node (ref "U21") (pin "3") (pinfunction "~{WP}(IO2)_3") (pintype "bidirectional"))
      (node (ref "U9") (pin "144") (pinfunction "P504/QSPI_IO_2_144") (pintype "bidirectional"))
    )
    (net (code "88") (name "QSPI_D3") (class "Default")
      (node (ref "U21") (pin "7") (pinfunction "~{HOLD}(IO3)_7") (pintype "bidirectional"))
      (node (ref "U9") (pin "145") (pinfunction "P505/QSPI_IO_3_145") (pintype "bidirectional"))
    )
    (net (code "89") (name "QSPI_SCK") (class "Default")
      (node (ref "U21") (pin "6") (pinfunction "SCK_6") (pintype "input"))
      (node (ref "U9") (pin "140") (pinfunction "P500/QSPI_CLK_140") (pintype "bidirectional"))
    )
    (net (code "90") (name "RESET#") (class "Default")
      (node (ref "J4") (pin "15") (pinfunction "15_15") (pintype "passive"))
      (node (ref "R17") (pin "7") (pinfunction "2_7") (pintype "passive"))
      (node (ref "U11") (pin "1") (pinfunction "RESET*_1") (pintype "bidirectional"))
      (node (ref "U9") (pin "67") (pinfunction "~{RESET}_67") (pintype "bidirectional"))
    )
    (net (code "91") (name "RY{slash}BY#") (class "Default")
      (node (ref "J2") (pin "17") (pinfunction "17_17") (pintype "bidirectional"))
      (node (ref "U9") (pin "169") (pinfunction "P000_169") (pintype "bidirectional"))
    )
    (net (code "92") (name "SCLK") (class "Default")
      (node (ref "U1") (pin "5") (pinfunction "SCLK_5") (pintype "input"))
      (node (ref "U2") (pin "5") (pinfunction "SCLK_5") (pintype "input"))
      (node (ref "U7") (pin "5") (pinfunction "SCLK_5") (pintype "input"))
      (node (ref "U8") (pin "5") (pinfunction "SCLK_5") (pintype "input"))
      (node (ref "U9") (pin "167") (pinfunction "P002_167") (pintype "bidirectional"))
    )
    (net (code "93") (name "SPARE_AIN") (class "Default")
      (node (ref "R9") (pin "1") (pinfunction "P$1_1") (pintype "bidirectional"))
      (node (ref "SPARE_AIN") (pin "1") (pinfunction "TP_1") (pintype "input"))
      (node (ref "U5") (pin "14") (pinfunction "OUT_14") (pintype "output"))
    )
    (net (code "94") (name "SPARE_DAC") (class "Default")
      (node (ref "U8") (pin "4") (pinfunction "DIN_4") (pintype "input"))
      (node (ref "U9") (pin "44") (pinfunction "P407/SDA0_B_44") (pintype "bidirectional"))
    )
    (net (code "95") (name "SYNC") (class "Default")
      (node (ref "U1") (pin "6") (pinfunction "SYNC_6") (pintype "input"))
      (node (ref "U2") (pin "6") (pinfunction "SYNC_6") (pintype "input"))
      (node (ref "U7") (pin "6") (pinfunction "SYNC_6") (pintype "input"))
      (node (ref "U8") (pin "6") (pinfunction "SYNC_6") (pintype "input"))
      (node (ref "U9") (pin "168") (pinfunction "P001_168") (pintype "bidirectional"))
    )
    (net (code "96") (name "TCK_SWCLK") (class "Default")
      (node (ref "J4") (pin "9") (pinfunction "9_9") (pintype "passive"))
      (node (ref "R20") (pin "1") (pinfunction "1_1") (pintype "passive"))
      (node (ref "U9") (pin "88") (pinfunction "P300/TCK/SWCLK_88") (pintype "bidirectional"))
    )
    (net (code "97") (name "TDI") (class "Default")
      (node (ref "J4") (pin "5") (pinfunction "5_5") (pintype "passive"))
      (node (ref "R20") (pin "4") (pinfunction "1_4") (pintype "passive"))
      (node (ref "U9") (pin "91") (pinfunction "P110/TDI_91") (pintype "bidirectional"))
    )
    (net (code "98") (name "TDO") (class "Default")
      (node (ref "J4") (pin "13") (pinfunction "13_13") (pintype "passive"))
      (node (ref "R20") (pin "3") (pinfunction "1_3") (pintype "passive"))
      (node (ref "U9") (pin "90") (pinfunction "P109/TDO_90") (pintype "bidirectional"))
    )
    (net (code "99") (name "TMS_SWDIO") (class "Default")
      (node (ref "J4") (pin "7") (pinfunction "7_7") (pintype "passive"))
      (node (ref "R20") (pin "2") (pinfunction "1_2") (pintype "passive"))
      (node (ref "U9") (pin "89") (pinfunction "P108/TMS/SWDIO_89") (pintype "bidirectional"))
    )
    (net (code "100") (name "USB_DM") (class "Default")
      (node (ref "R14") (pin "1") (pinfunction "P$1_1") (pintype "bidirectional"))
      (node (ref "U9") (pin "31") (pinfunction "USBHS_DM_31") (pintype "bidirectional"))
    )
    (net (code "101") (name "USB_DP") (class "Default")
      (node (ref "R15") (pin "1") (pinfunction "P$1_1") (pintype "bidirectional"))
      (node (ref "U9") (pin "32") (pinfunction "USBHS_DP_32") (pintype "bidirectional"))
    )
    (net (code "102") (name "USB_OVER_CRNT") (class "Default")
      (node (ref "R11") (pin "2") (pinfunction "P$2_2") (pintype "bidirectional"))
      (node (ref "R13") (pin "2") (pinfunction "P$2_2") (pintype "bidirectional"))
      (node (ref "U10") (pin "5") (pinfunction "OCN_5") (pintype "bidirectional"))
      (node (ref "U9") (pin "15") (pinfunction "P707/USBHS_OVER_CRNT_15") (pintype "bidirectional"))
    )
    (net (code "103") (name "USB_VBUS_EN") (class "Default")
      (node (ref "U10") (pin "4") (pinfunction "EN_4") (pintype "bidirectional"))
      (node (ref "U9") (pin "16") (pinfunction "PB00/USBHS_VBUS_EN_16") (pintype "bidirectional"))
    )
    (net (code "104") (name "VCC") (class "Default")
      (node (ref "C10") (pin "1") (pinfunction "P$1_1") (pintype "bidirectional"))
      (node (ref "C11") (pin "1") (pinfunction "P$1_1") (pintype "bidirectional"))
      (node (ref "C12") (pin "1") (pinfunction "P$1_1") (pintype "bidirectional"))
      (node (ref "C13") (pin "2") (pinfunction "2_2") (pintype "passive"))
      (node (ref "C14") (pin "2") (pinfunction "2_2") (pintype "passive"))
      (node (ref "C15") (pin "1") (pinfunction "P$1_1") (pintype "bidirectional"))
      (node (ref "C16") (pin "1") (pinfunction "P$1_1") (pintype "bidirectional"))
      (node (ref "C23") (pin "2") (pinfunction "2_2") (pintype "passive"))
      (node (ref "C25") (pin "2") (pinfunction "2_2") (pintype "passive"))
      (node (ref "C26") (pin "2") (pinfunction "2_2") (pintype "passive"))
      (node (ref "C27") (pin "2") (pinfunction "2_2") (pintype "passive"))
      (node (ref "C29") (pin "2") (pinfunction "2_2") (pintype "passive"))
      (node (ref "C30") (pin "2") (pinfunction "2_2") (pintype "passive"))
      (node (ref "C31") (pin "2") (pinfunction "2_2") (pintype "passive"))
      (node (ref "C32") (pin "2") (pinfunction "2_2") (pintype "passive"))
      (node (ref "C33") (pin "2") (pinfunction "2_2") (pintype "passive"))
      (node (ref "C34") (pin "2") (pinfunction "2_2") (pintype "passive"))
      (node (ref "C35") (pin "2") (pinfunction "2_2") (pintype "passive"))
      (node (ref "C4") (pin "2") (pinfunction "2_2") (pintype "passive"))
      (node (ref "C5") (pin "2") (pinfunction "2_2") (pintype "passive"))
      (node (ref "C8") (pin "1") (pinfunction "P$1_1") (pintype "bidirectional"))
      (node (ref "C9") (pin "1") (pinfunction "P$1_1") (pintype "bidirectional"))
      (node (ref "J2") (pin "29") (pinfunction "29_29") (pintype "bidirectional"))
      (node (ref "J2") (pin "43") (pinfunction "43_43") (pintype "bidirectional"))
      (node (ref "J4") (pin "1") (pinfunction "1_1") (pintype "passive"))
      (node (ref "R11") (pin "1") (pinfunction "P$1_1") (pintype "bidirectional"))
      (node (ref "R17") (pin "2") (pinfunction "1_2") (pintype "passive"))
      (node (ref "R17") (pin "3") (pinfunction "1_3") (pintype "passive"))
      (node (ref "R17") (pin "4") (pinfunction "1_4") (pintype "passive"))
      (node (ref "R20") (pin "5") (pinfunction "2_5") (pintype "passive"))
      (node (ref "R20") (pin "6") (pinfunction "2_6") (pintype "passive"))
      (node (ref "R20") (pin "7") (pinfunction "2_7") (pintype "passive"))
      (node (ref "R20") (pin "8") (pinfunction "2_8") (pintype "passive"))
      (node (ref "U1") (pin "3") (pinfunction "VA_3") (pintype "power_in"))
      (node (ref "U11") (pin "2") (pinfunction "VCC_2") (pintype "bidirectional"))
      (node (ref "U2") (pin "3") (pinfunction "VA_3") (pintype "power_in"))
      (node (ref "U21") (pin "8") (pinfunction "VCC_8") (pintype "power_in"))
      (node (ref "U4") (pin "8") (pinfunction "V_8") (pintype "bidirectional"))
      (node (ref "U6") (pin "3") (pinfunction "OUT_3") (pintype "passive"))
      (node (ref "U7") (pin "3") (pinfunction "VA_3") (pintype "power_in"))
      (node (ref "U8") (pin "3") (pinfunction "VA_3") (pintype "power_in"))
      (node (ref "U9") (pin "110") (pinfunction "VCC5_110") (pintype "bidirectional"))
      (node (ref "U9") (pin "123") (pinfunction "VCC6_123") (pintype "bidirectional"))
      (node (ref "U9") (pin "138") (pinfunction "VCC7_138") (pintype "bidirectional"))
      (node (ref "U9") (pin "149") (pinfunction "VCC8_149") (pintype "bidirectional"))
      (node (ref "U9") (pin "154") (pinfunction "VREFH_154") (pintype "bidirectional"))
      (node (ref "U9") (pin "155") (pinfunction "AVCC0_155") (pintype "bidirectional"))
      (node (ref "U9") (pin "158") (pinfunction "VREFH0_158") (pintype "bidirectional"))
      (node (ref "U9") (pin "171") (pinfunction "VCC9_171") (pintype "bidirectional"))
      (node (ref "U9") (pin "25") (pinfunction "VCC1_25") (pintype "bidirectional"))
      (node (ref "U9") (pin "26") (pinfunction "AVCC_USBHS_26") (pintype "bidirectional"))
      (node (ref "U9") (pin "34") (pinfunction "VCC_USBHS_34") (pintype "bidirectional"))
      (node (ref "U9") (pin "48") (pinfunction "VCC_USB_48") (pintype "bidirectional"))
      (node (ref "U9") (pin "61") (pinfunction "VCC2_61") (pintype "bidirectional"))
      (node (ref "U9") (pin "84") (pinfunction "VCC3_84") (pintype "bidirectional"))
      (node (ref "U9") (pin "97") (pinfunction "VCC4_97") (pintype "bidirectional"))
      (node (ref "VCC") (pin "1") (pinfunction "TP_1") (pintype "input"))
      (node (ref "Y1") (pin "4") (pinfunction "VDD_4") (pintype "power_in"))
    )
    (net (code "105") (name "WE#") (class "Default")
      (node (ref "J2") (pin "13") (pinfunction "13_13") (pintype "bidirectional"))
      (node (ref "U9") (pin "166") (pinfunction "P003_166") (pintype "bidirectional"))
    )
    (net (code "106") (name "WP_ACC_AIN") (class "Default")
      (node (ref "J2") (pin "16") (pinfunction "16_16") (pintype "bidirectional"))
      (node (ref "R4") (pin "2") (pinfunction "P$2_2") (pintype "bidirectional"))
      (node (ref "U5") (pin "7") (pinfunction "OUT_7") (pintype "output"))
    )
    (net (code "107") (name "WP_ACC_DAC") (class "Default")
      (node (ref "U2") (pin "4") (pinfunction "DIN_4") (pintype "input"))
      (node (ref "U9") (pin "5") (pinfunction "P404_5") (pintype "bidirectional"))
    )
    (net (code "108") (name "unconnected-(J2-Pad27)") (class "Default")
      (node (ref "J2") (pin "27") (pinfunction "27_27") (pintype "bidirectional"))
    )
    (net (code "109") (name "unconnected-(J2-Pad28)") (class "Default")
      (node (ref "J2") (pin "28") (pinfunction "28_28") (pintype "bidirectional"))
    )
    (net (code "110") (name "unconnected-(J2-Pad30)") (class "Default")
      (node (ref "J2") (pin "30") (pinfunction "30_30") (pintype "bidirectional"))
    )
    (net (code "111") (name "unconnected-(J2-PadMH1)") (class "Default")
      (node (ref "J2") (pin "MH1") (pinfunction "MH1_MH1") (pintype "bidirectional"))
    )
    (net (code "112") (name "unconnected-(J2-PadMH2)") (class "Default")
      (node (ref "J2") (pin "MH2") (pinfunction "MH2_MH2") (pintype "bidirectional"))
    )
    (net (code "113") (name "unconnected-(J4-Pad2)") (class "Default")
      (node (ref "J4") (pin "2") (pinfunction "2_2") (pintype "passive"))
    )
    (net (code "114") (name "unconnected-(J4-Pad3)") (class "Default")
      (node (ref "J4") (pin "3") (pinfunction "3_3") (pintype "passive"))
    )
    (net (code "115") (name "unconnected-(J4-Pad11)") (class "Default")
      (node (ref "J4") (pin "11") (pinfunction "11_11") (pintype "passive"))
    )
    (net (code "116") (name "unconnected-(J4-Pad17)") (class "Default")
      (node (ref "J4") (pin "17") (pinfunction "17_17") (pintype "passive"))
    )
    (net (code "117") (name "unconnected-(J4-Pad19)") (class "Default")
      (node (ref "J4") (pin "19") (pinfunction "19_19") (pintype "passive"))
    )
    (net (code "118") (name "unconnected-(U9-P005-Pad164)") (class "Default")
      (node (ref "U9") (pin "164") (pinfunction "P005_164") (pintype "bidirectional"))
    )
    (net (code "119") (name "unconnected-(U9-P006-Pad163)") (class "Default")
      (node (ref "U9") (pin "163") (pinfunction "P006_163") (pintype "bidirectional"))
    )
    (net (code "120") (name "unconnected-(U9-P007-Pad162)") (class "Default")
      (node (ref "U9") (pin "162") (pinfunction "P007_162") (pintype "bidirectional"))
    )
    (net (code "121") (name "unconnected-(U9-P008-Pad161)") (class "Default")
      (node (ref "U9") (pin "161") (pinfunction "P008_161") (pintype "bidirectional"))
    )
    (net (code "122") (name "unconnected-(U9-P009-Pad160)") (class "Default")
      (node (ref "U9") (pin "160") (pinfunction "P009_160") (pintype "bidirectional"))
    )
    (net (code "123") (name "unconnected-(U9-P010-Pad159)") (class "Default")
      (node (ref "U9") (pin "159") (pinfunction "P010_159") (pintype "bidirectional"))
    )
    (net (code "124") (name "unconnected-(U9-P014{slash}DAC_0-Pad152)") (class "Default")
      (node (ref "U9") (pin "152") (pinfunction "P014/DAC_0_152") (pintype "bidirectional"))
    )
    (net (code "125") (name "unconnected-(U9-P015{slash}DAC_1-Pad151)") (class "Default")
      (node (ref "U9") (pin "151") (pinfunction "P015/DAC_1_151") (pintype "bidirectional"))
    )
    (net (code "126") (name "unconnected-(U9-P202{slash}RXD9_A-Pad54)") (class "Default")
      (node (ref "U9") (pin "54") (pinfunction "P202/RXD9_A_54") (pintype "bidirectional"))
    )
    (net (code "127") (name "unconnected-(U9-P206{slash}SD0_DAT2-Pad50)") (class "Default")
      (node (ref "U9") (pin "50") (pinfunction "P206/SD0_DAT2_50") (pintype "bidirectional"))
    )
    (net (code "128") (name "unconnected-(U9-P213{slash}XTAL{slash}TXD-Pad23)") (class "Default")
      (node (ref "U9") (pin "23") (pinfunction "P213/XTAL/TXD_23") (pintype "bidirectional"))
    )
    (net (code "129") (name "unconnected-(U9-P311{slash}RAS#-Pad75)") (class "Default")
      (node (ref "U9") (pin "75") (pinfunction "P311/RAS#_75") (pintype "bidirectional"))
    )
    (net (code "130") (name "unconnected-(U9-P312{slash}CAS#-Pad74)") (class "Default")
      (node (ref "U9") (pin "74") (pinfunction "P312/CAS#_74") (pintype "bidirectional"))
    )
    (net (code "131") (name "unconnected-(U9-P400{slash}SCK7_A-Pad1)") (class "Default")
      (node (ref "U9") (pin "1") (pinfunction "P400/SCK7_A_1") (pintype "bidirectional"))
    )
    (net (code "132") (name "unconnected-(U9-P401{slash}MOSI7_A-Pad2)") (class "Default")
      (node (ref "U9") (pin "2") (pinfunction "P401/MOSI7_A_2") (pintype "bidirectional"))
    )
    (net (code "133") (name "unconnected-(U9-P402{slash}MISO7_A-Pad3)") (class "Default")
      (node (ref "U9") (pin "3") (pinfunction "P402/MISO7_A_3") (pintype "bidirectional"))
    )
    (net (code "134") (name "unconnected-(U9-P403{slash}SS7_A-Pad4)") (class "Default")
      (node (ref "U9") (pin "4") (pinfunction "P403/SS7_A_4") (pintype "bidirectional"))
    )
    (net (code "135") (name "unconnected-(U9-P410{slash}SD0_DAT1-Pad41)") (class "Default")
      (node (ref "U9") (pin "41") (pinfunction "P410/SD0_DAT1_41") (pintype "bidirectional"))
    )
    (net (code "136") (name "unconnected-(U9-P411{slash}SD0_DAT0-Pad40)") (class "Default")
      (node (ref "U9") (pin "40") (pinfunction "P411/SD0_DAT0_40") (pintype "bidirectional"))
    )
    (net (code "137") (name "unconnected-(U9-P412{slash}SD0_CMD-Pad39)") (class "Default")
      (node (ref "U9") (pin "39") (pinfunction "P412/SD0_CMD_39") (pintype "bidirectional"))
    )
    (net (code "138") (name "unconnected-(U9-P413{slash}SD0_CLK-Pad38)") (class "Default")
      (node (ref "U9") (pin "38") (pinfunction "P413/SD0_CLK_38") (pintype "bidirectional"))
    )
    (net (code "139") (name "unconnected-(U9-P414-Pad37)") (class "Default")
      (node (ref "U9") (pin "37") (pinfunction "P414_37") (pintype "bidirectional"))
    )
    (net (code "140") (name "unconnected-(U9-P415-Pad36)") (class "Default")
      (node (ref "U9") (pin "36") (pinfunction "P415_36") (pintype "bidirectional"))
    )
    (net (code "141") (name "unconnected-(U9-P506{slash}TXD6_B-Pad146)") (class "Default")
      (node (ref "U9") (pin "146") (pinfunction "P506/TXD6_B_146") (pintype "bidirectional"))
    )
    (net (code "142") (name "unconnected-(U9-P511{slash}RXD4_B{slash}SCL4_B-Pad176)") (class "Default")
      (node (ref "U9") (pin "176") (pinfunction "P511/RXD4_B/SCL4_B_176") (pintype "bidirectional"))
    )
    (net (code "143") (name "unconnected-(U9-P512{slash}TXD4_B{slash}SDA4_B-Pad175)") (class "Default")
      (node (ref "U9") (pin "175") (pinfunction "P512/TXD4_B/SDA4_B_175") (pintype "bidirectional"))
    )
    (net (code "144") (name "unconnected-(U9-P513-Pad174)") (class "Default")
      (node (ref "U9") (pin "174") (pinfunction "P513_174") (pintype "bidirectional"))
    )
    (net (code "145") (name "unconnected-(U9-P600-Pad122)") (class "Default")
      (node (ref "U9") (pin "122") (pinfunction "P600_122") (pintype "bidirectional"))
    )
    (net (code "146") (name "unconnected-(U9-P601{slash}DQM0-Pad121)") (class "Default")
      (node (ref "U9") (pin "121") (pinfunction "P601/DQM0_121") (pintype "bidirectional"))
    )
    (net (code "147") (name "unconnected-(U9-P602{slash}SDCLK-Pad120)") (class "Default")
      (node (ref "U9") (pin "120") (pinfunction "P602/SDCLK_120") (pintype "bidirectional"))
    )
    (net (code "148") (name "unconnected-(U9-P606{slash}LCD_DATA_3-Pad116)") (class "Default")
      (node (ref "U9") (pin "116") (pinfunction "P606/LCD_DATA_3_116") (pintype "bidirectional"))
    )
    (net (code "149") (name "unconnected-(U9-P607{slash}LCD_DATA_4-Pad115)") (class "Default")
      (node (ref "U9") (pin "115") (pinfunction "P607/LCD_DATA_4_115") (pintype "bidirectional"))
    )
    (net (code "150") (name "unconnected-(U9-P609{slash}CKE-Pad100)") (class "Default")
      (node (ref "U9") (pin "100") (pinfunction "P609/CKE_100") (pintype "bidirectional"))
    )
    (net (code "151") (name "unconnected-(U9-P610{slash}WE#-Pad101)") (class "Default")
      (node (ref "U9") (pin "101") (pinfunction "P610/WE#_101") (pintype "bidirectional"))
    )
    (net (code "152") (name "unconnected-(U9-P611{slash}SDCS#-Pad102)") (class "Default")
      (node (ref "U9") (pin "102") (pinfunction "P611/SDCS#_102") (pintype "bidirectional"))
    )
    (net (code "153") (name "unconnected-(U9-P615{slash}LCD_DATA_10-Pad106)") (class "Default")
      (node (ref "U9") (pin "106") (pinfunction "P615/LCD_DATA_10_106") (pintype "bidirectional"))
    )
    (net (code "154") (name "unconnected-(U9-P701{slash}GTIOC_5B_B-Pad9)") (class "Default")
      (node (ref "U9") (pin "9") (pinfunction "P701/GTIOC_5B_B_9") (pintype "bidirectional"))
    )
    (net (code "155") (name "unconnected-(U9-P706{slash}IRQ_7-Pad14)") (class "Default")
      (node (ref "U9") (pin "14") (pinfunction "P706/IRQ_7_14") (pintype "bidirectional"))
    )
    (net (code "156") (name "unconnected-(U9-P802{slash}LCD_DATA_2-Pad135)") (class "Default")
      (node (ref "U9") (pin "135") (pinfunction "P802/LCD_DATA_2_135") (pintype "bidirectional"))
    )
    (net (code "157") (name "unconnected-(U9-P803{slash}LCD_DATA_1-Pad136)") (class "Default")
      (node (ref "U9") (pin "136") (pinfunction "P803/LCD_DATA_1_136") (pintype "bidirectional"))
    )
    (net (code "158") (name "unconnected-(U9-P804{slash}LCD_DATA_0-Pad137)") (class "Default")
      (node (ref "U9") (pin "137") (pinfunction "P804/LCD_DATA_0_137") (pintype "bidirectional"))
    )
    (net (code "159") (name "unconnected-(U9-P901{slash}LCD_DATA_15-Pad59)") (class "Default")
      (node (ref "U9") (pin "59") (pinfunction "P901/LCD_DATA_15_59") (pintype "bidirectional"))
    )
    (net (code "160") (name "unconnected-(U9-P905{slash}LCD_DATA_11-Pad73)") (class "Default")
      (node (ref "U9") (pin "73") (pinfunction "P905/LCD_DATA_11_73") (pintype "bidirectional"))
    )
    (net (code "161") (name "unconnected-(U9-P906{slash}LCD_DATA_12-Pad72)") (class "Default")
      (node (ref "U9") (pin "72") (pinfunction "P906/LCD_DATA_12_72") (pintype "bidirectional"))
    )
    (net (code "162") (name "unconnected-(U9-P907{slash}LCD_DATA_13-Pad71)") (class "Default")
      (node (ref "U9") (pin "71") (pinfunction "P907/LCD_DATA_13_71") (pintype "bidirectional"))
    )
    (net (code "163") (name "unconnected-(U9-P908{slash}LCD_DATA_14-Pad70)") (class "Default")
      (node (ref "U9") (pin "70") (pinfunction "P908/LCD_DATA_14_70") (pintype "bidirectional"))
    )
    (net (code "164") (name "unconnected-(U9-PA00{slash}LCD_DATA_5-Pad114)") (class "Default")
      (node (ref "U9") (pin "114") (pinfunction "PA00/LCD_DATA_5_114") (pintype "bidirectional"))
    )
    (net (code "165") (name "unconnected-(U9-PA01{slash}LCD_DATA_6-Pad113)") (class "Default")
      (node (ref "U9") (pin "113") (pinfunction "PA01/LCD_DATA_6_113") (pintype "bidirectional"))
    )
    (net (code "166") (name "unconnected-(U9-PA08{slash}LCD_DATA_9-Pad107)") (class "Default")
      (node (ref "U9") (pin "107") (pinfunction "PA08/LCD_DATA_9_107") (pintype "bidirectional"))
    )
    (net (code "167") (name "unconnected-(U9-PA09{slash}LCD_DATA_8-Pad108)") (class "Default")
      (node (ref "U9") (pin "108") (pinfunction "PA09/LCD_DATA_8_108") (pintype "bidirectional"))
    )
    (net (code "168") (name "unconnected-(U9-PA10{slash}LCD_DATA_7-Pad109)") (class "Default")
      (node (ref "U9") (pin "109") (pinfunction "PA10/LCD_DATA_7_109") (pintype "bidirectional"))
    )
    (net (code "169") (name "unconnected-(U9-PB01{slash}CTS3-Pad17)") (class "Default")
      (node (ref "U9") (pin "17") (pinfunction "PB01/CTS3_17") (pintype "bidirectional"))
    )
    (net (code "170") (name "unconnected-(U9-USB_DM-Pad46)") (class "Default")
      (node (ref "U9") (pin "46") (pinfunction "USB_DM_46") (pintype "bidirectional"))
    )
    (net (code "171") (name "unconnected-(U9-USB_DP-Pad47)") (class "Default")
      (node (ref "U9") (pin "47") (pinfunction "USB_DP_47") (pintype "bidirectional"))
    )
    (net (code "172") (name "unconnected-(U9-VBATT-Pad18)") (class "Default")
      (node (ref "U9") (pin "18") (pinfunction "VBATT_18") (pintype "bidirectional"))
    )
    (net (code "173") (name "unconnected-(U9-XCIN-Pad20)") (class "Default")
      (node (ref "U9") (pin "20") (pinfunction "XCIN_20") (pintype "bidirectional"))
    )
    (net (code "174") (name "unconnected-(U9-XCOUT-Pad21)") (class "Default")
      (node (ref "U9") (pin "21") (pinfunction "XCOUT_21") (pintype "bidirectional"))
    )
    (net (code "175") (name "unconnected-(Y1-CTL-Pad1)") (class "Default")
      (node (ref "Y1") (pin "1") (pinfunction "CTL_1") (pintype "passive"))
    )
  )
)
